# myPlant.net
KiCad netlist of a schematic drawn in EAGLE
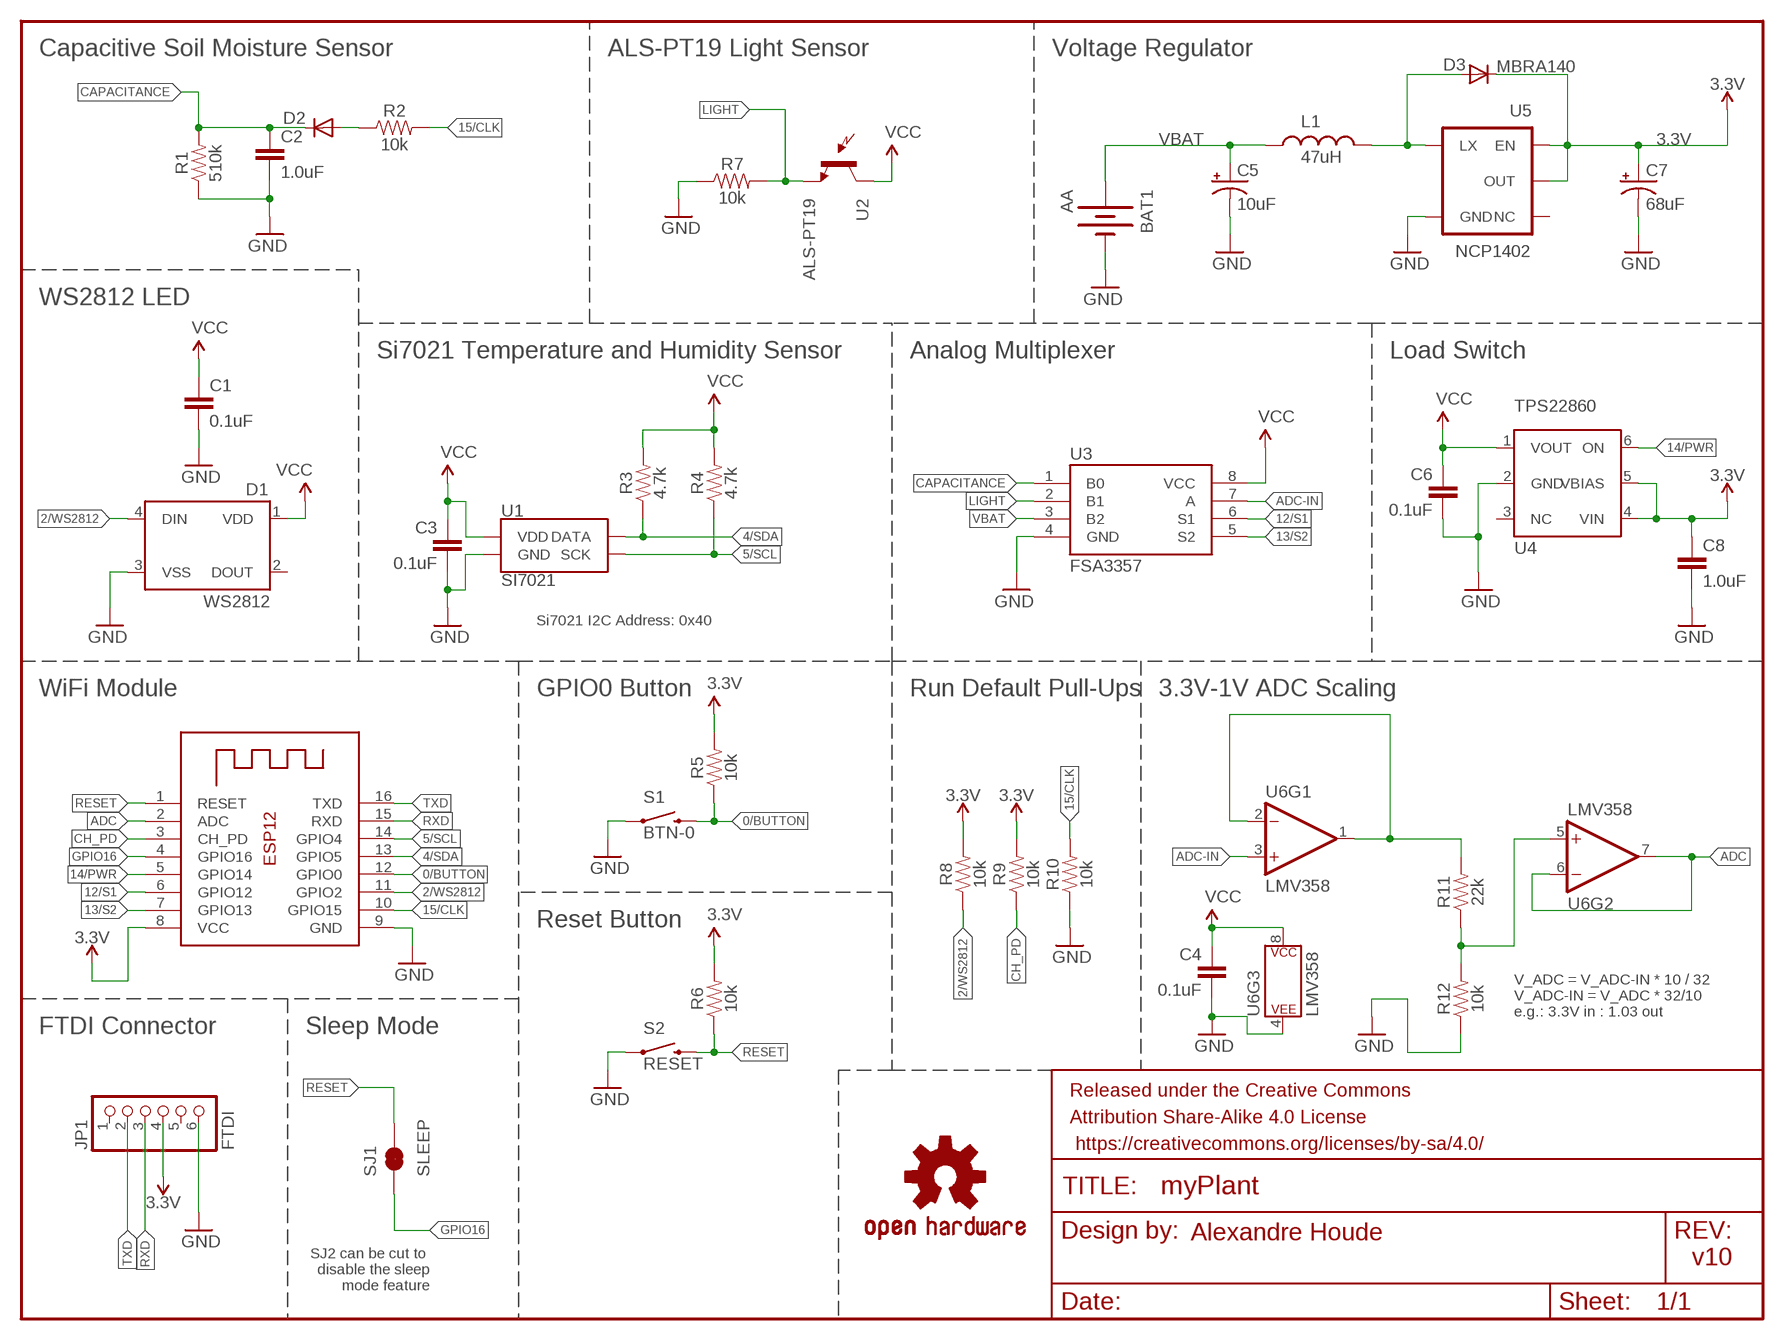
[diagram p0: schematic, sheet 1]

(export (version "E")
  (design (tool "Eeschema 10.0.6"))
  (components
    (comp (ref "BAT1")
      (value "AA")
      (footprint "eagle-import:BATTERY-AA-KIT")
      (libsource (lib "eagle-import") (part "BATTERYAA-KIT"))
    )
    (comp (ref "C1")
      (value "0.1uF")
      (footprint "eagle-import:0603")
      (libsource (lib "eagle-import") (part "0.1UF-0603-25V-(+80/-20%)"))
    )
    (comp (ref "C2")
      (value "1.0uF")
      (footprint "eagle-import:0603")
      (libsource (lib "eagle-import") (part "1.0UF-0603-16V-10%"))
    )
    (comp (ref "C3")
      (value "0.1uF")
      (footprint "eagle-import:0603")
      (libsource (lib "eagle-import") (part "0.1UF-0603-25V-(+80/-20%)"))
    )
    (comp (ref "C4")
      (value "0.1uF")
      (footprint "eagle-import:0603")
      (libsource (lib "eagle-import") (part "0.1UF-0603-25V-(+80/-20%)"))
    )
    (comp (ref "C5")
      (value "10uF")
      (footprint "eagle-import:EIA3216")
      (libsource (lib "eagle-import") (part "CAP_POL1206"))
    )
    (comp (ref "C6")
      (value "0.1uF")
      (footprint "eagle-import:0603")
      (libsource (lib "eagle-import") (part "0.1UF-0603-25V-(+80/-20%)"))
    )
    (comp (ref "C7")
      (value "68uF")
      (footprint "eagle-import:EIA3528")
      (libsource (lib "eagle-import") (part "CAP_POL3528"))
    )
    (comp (ref "C8")
      (value "1.0uF")
      (footprint "eagle-import:0603")
      (libsource (lib "eagle-import") (part "1.0UF-0603-16V-10%"))
    )
    (comp (ref "D1")
      (value "WS2812")
      (footprint "eagle-import:WS2812B")
      (libsource (lib "eagle-import") (part "WS2812B"))
    )
    (comp (ref "D2")
      (value "DIODE-SCHOTTKY_")
      (footprint "eagle-import:SOD-523")
      (libsource (lib "eagle-import") (part "DIODESOD-523"))
    )
    (comp (ref "D3")
      (value "MBRA140")
      (footprint "eagle-import:SMA-DIODE")
      (libsource (lib "eagle-import") (part "DIODESMA"))
    )
    (comp (ref "FRAME1")
      (value "FRAME-LETTER")
      (footprint "eagle-import:CREATIVE_COMMONS")
      (libsource (lib "eagle-import") (part "FRAME-LETTER"))
    )
    (comp (ref "JP1")
      (value "FTDI")
      (footprint "eagle-import:1X06_ROUND_70")
      (libsource (lib "eagle-import") (part "HEADER-1X670MIL"))
    )
    (comp (ref "L1")
      (value "47uH")
      (footprint "eagle-import:CR54")
      (libsource (lib "eagle-import") (part "INDUCTORCR54"))
    )
    (comp (ref "LOGO2")
      (value "OSHW-LOGOS")
      (footprint "eagle-import:OSHW-LOGO-S")
      (libsource (lib "eagle-import") (part "OSHW-LOGOS"))
    )
    (comp (ref "R1")
      (value "510k")
      (footprint "eagle-import:0603")
      (libsource (lib "eagle-import") (part "10KOHM-0603-1/10W-1%"))
    )
    (comp (ref "R2")
      (value "10k")
      (footprint "eagle-import:0603")
      (libsource (lib "eagle-import") (part "10KOHM-0603-1/10W-1%"))
    )
    (comp (ref "R3")
      (value "4.7k")
      (footprint "eagle-import:0603")
      (libsource (lib "eagle-import") (part "4.7KOHM-0603-1/10W-1%"))
    )
    (comp (ref "R4")
      (value "4.7k")
      (footprint "eagle-import:0603")
      (libsource (lib "eagle-import") (part "4.7KOHM-0603-1/10W-1%"))
    )
    (comp (ref "R5")
      (value "10k")
      (footprint "eagle-import:0603")
      (libsource (lib "eagle-import") (part "10KOHM-0603-1/10W-1%"))
    )
    (comp (ref "R6")
      (value "10k")
      (footprint "eagle-import:0603")
      (libsource (lib "eagle-import") (part "10KOHM-0603-1/10W-1%"))
    )
    (comp (ref "R7")
      (value "10k")
      (footprint "eagle-import:0603")
      (libsource (lib "eagle-import") (part "10KOHM-0603-1/10W-1%"))
    )
    (comp (ref "R8")
      (value "10k")
      (footprint "eagle-import:0603")
      (libsource (lib "eagle-import") (part "10KOHM-0603-1/10W-1%"))
    )
    (comp (ref "R9")
      (value "10k")
      (footprint "eagle-import:0603")
      (libsource (lib "eagle-import") (part "10KOHM-0603-1/10W-1%"))
    )
    (comp (ref "R10")
      (value "10k")
      (footprint "eagle-import:0603")
      (libsource (lib "eagle-import") (part "10KOHM-0603-1/10W-1%"))
    )
    (comp (ref "R11")
      (value "22k")
      (footprint "eagle-import:0603")
      (libsource (lib "eagle-import") (part "22KOHM-0603-1/10W-1%"))
    )
    (comp (ref "R12")
      (value "10k")
      (footprint "eagle-import:0603")
      (libsource (lib "eagle-import") (part "10KOHM-0603-1/10W-1%"))
    )
    (comp (ref "S1")
      (value "BTN-0")
      (footprint "eagle-import:TACTILE_SWITCH_SMD_4.6X2.8MM")
      (libsource (lib "eagle-import") (part "SWITCH-MOMENTARY-2SMD-4.6X2.8MM"))
    )
    (comp (ref "S2")
      (value "RESET")
      (footprint "eagle-import:TACTILE_SWITCH_SMD_4.6X2.8MM")
      (libsource (lib "eagle-import") (part "SWITCH-MOMENTARY-2SMD-4.6X2.8MM"))
    )
    (comp (ref "SJ1")
      (value "SLEEP")
      (footprint "eagle-import:PAD-JUMPER-2-NC_BY_TRACE_YES_SILK")
      (libsource (lib "eagle-import") (part "JUMPER-PAD-2-NC_BY_TRACE"))
    )
    (comp (ref "U1")
      (value "SI7021")
      (footprint "eagle-import:DFN-6-3X3-SI7021")
      (libsource (lib "eagle-import") (part "SI7021"))
    )
    (comp (ref "U2")
      (value "ALS-PT19")
      (footprint "eagle-import:ALS-PT19")
      (libsource (lib "eagle-import") (part "LIGHTSENSORALS"))
    )
    (comp (ref "U3")
      (value "FSA3357")
      (footprint "eagle-import:US8")
      (libsource (lib "eagle-import") (part "FSA3357"))
    )
    (comp (ref "U4")
      (value "TPS22860")
      (footprint "eagle-import:SOT23-6")
      (libsource (lib "eagle-import") (part "TPS22860"))
    )
    (comp (ref "U5")
      (value "NCP1402")
      (footprint "eagle-import:SOT23-5")
      (libsource (lib "eagle-import") (part "V_REG_NCP1400SOT23-5"))
    )
    (comp (ref "U6")
      (value "LMV358")
      (footprint "eagle-import:MSOP8")
      (libsource (lib "eagle-import") (part "LMV358"))
    )
    (comp (ref "X1")
      (value "ESP-12")
      (footprint "eagle-import:ESP-12")
      (libsource (lib "eagle-import") (part "ESP-12"))
    )
  )
  (nets
    (net (code "1") (name "0{slash}BUTTON") (class "Default")
      (node (ref "R5") (pin "1") (pinfunction "1_1") (pintype "passive"))
      (node (ref "S1") (pin "3") (pinfunction "2_3") (pintype "passive"))
      (node (ref "S1") (pin "4") (pinfunction "2_4") (pintype "passive"))
      (node (ref "X1") (pin "12") (pinfunction "GPIO0_12") (pintype "bidirectional"))
    )
    (net (code "2") (name "2{slash}WS2812") (class "Default")
      (node (ref "D1") (pin "4") (pinfunction "DIN_4") (pintype "input"))
      (node (ref "R8") (pin "1") (pinfunction "1_1") (pintype "passive"))
      (node (ref "X1") (pin "11") (pinfunction "GPIO2_11") (pintype "bidirectional"))
    )
    (net (code "3") (name "3.3V") (class "Default")
      (node (ref "C7") (pin "A") (pinfunction "+_A") (pintype "passive"))
      (node (ref "C8") (pin "1") (pinfunction "1_1") (pintype "passive"))
      (node (ref "D3") (pin "C") (pinfunction "C_C") (pintype "passive"))
      (node (ref "JP1") (pin "4") (pinfunction "4_4") (pintype "passive"))
      (node (ref "R5") (pin "2") (pinfunction "2_2") (pintype "passive"))
      (node (ref "R6") (pin "2") (pinfunction "2_2") (pintype "passive"))
      (node (ref "R8") (pin "2") (pinfunction "2_2") (pintype "passive"))
      (node (ref "R9") (pin "2") (pinfunction "2_2") (pintype "passive"))
      (node (ref "U4") (pin "4") (pinfunction "VIN_4") (pintype "bidirectional"))
      (node (ref "U4") (pin "5") (pinfunction "VBIAS_5") (pintype "bidirectional"))
      (node (ref "U5") (pin "1") (pinfunction "EN_1") (pintype "input"))
      (node (ref "U5") (pin "2") (pinfunction "OUT_2") (pintype "passive"))
      (node (ref "X1") (pin "8") (pinfunction "VCC_8") (pintype "power_in"))
    )
    (net (code "4") (name "4{slash}SDA") (class "Default")
      (node (ref "R3") (pin "1") (pinfunction "1_1") (pintype "passive"))
      (node (ref "U1") (pin "DATA") (pinfunction "DATA_DATA") (pintype "bidirectional"))
      (node (ref "X1") (pin "13") (pinfunction "GPIO5_13") (pintype "bidirectional"))
    )
    (net (code "5") (name "5{slash}SCL") (class "Default")
      (node (ref "R4") (pin "1") (pinfunction "1_1") (pintype "passive"))
      (node (ref "U1") (pin "SCK") (pinfunction "SCK_SCK") (pintype "input"))
      (node (ref "X1") (pin "14") (pinfunction "GPIO4_14") (pintype "bidirectional"))
    )
    (net (code "6") (name "12{slash}S1") (class "Default")
      (node (ref "U3") (pin "6") (pinfunction "S1_6") (pintype "bidirectional"))
      (node (ref "X1") (pin "6") (pinfunction "GPIO12_6") (pintype "bidirectional"))
    )
    (net (code "7") (name "13{slash}S2") (class "Default")
      (node (ref "U3") (pin "5") (pinfunction "S2_5") (pintype "bidirectional"))
      (node (ref "X1") (pin "7") (pinfunction "GPIO13_7") (pintype "bidirectional"))
    )
    (net (code "8") (name "14{slash}PWR") (class "Default")
      (node (ref "U4") (pin "6") (pinfunction "ON_6") (pintype "bidirectional"))
      (node (ref "X1") (pin "5") (pinfunction "GPIO14_5") (pintype "bidirectional"))
    )
    (net (code "9") (name "15{slash}CLK") (class "Default")
      (node (ref "R10") (pin "2") (pinfunction "2_2") (pintype "passive"))
      (node (ref "R2") (pin "2") (pinfunction "2_2") (pintype "passive"))
      (node (ref "X1") (pin "10") (pinfunction "GPIO15_10") (pintype "bidirectional"))
    )
    (net (code "10") (name "ADC") (class "Default")
      (node (ref "U6") (pin "6") (pinfunction "-IN_6") (pintype "input"))
      (node (ref "U6") (pin "7") (pinfunction "OUT_7") (pintype "output"))
      (node (ref "X1") (pin "2") (pinfunction "ADC_2") (pintype "passive"))
    )
    (net (code "11") (name "ADC-IN") (class "Default")
      (node (ref "U3") (pin "7") (pinfunction "A_7") (pintype "bidirectional"))
      (node (ref "U6") (pin "3") (pinfunction "+IN_3") (pintype "input"))
    )
    (net (code "12") (name "CAPACITANCE") (class "Default")
      (node (ref "C2") (pin "1") (pinfunction "1_1") (pintype "passive"))
      (node (ref "D2") (pin "K") (pinfunction "C_K") (pintype "passive"))
      (node (ref "R1") (pin "2") (pinfunction "2_2") (pintype "passive"))
      (node (ref "U3") (pin "1") (pinfunction "B0_1") (pintype "bidirectional"))
    )
    (net (code "13") (name "CH_PD") (class "Default")
      (node (ref "R9") (pin "1") (pinfunction "1_1") (pintype "passive"))
      (node (ref "X1") (pin "3") (pinfunction "CH_PD_3") (pintype "input"))
    )
    (net (code "14") (name "GND") (class "Default")
      (node (ref "BAT1") (pin "GND@1") (pinfunction "-_GND@1") (pintype "power_in"))
      (node (ref "C1") (pin "2") (pinfunction "2_2") (pintype "passive"))
      (node (ref "C2") (pin "2") (pinfunction "2_2") (pintype "passive"))
      (node (ref "C3") (pin "2") (pinfunction "2_2") (pintype "passive"))
      (node (ref "C4") (pin "2") (pinfunction "2_2") (pintype "passive"))
      (node (ref "C5") (pin "C") (pinfunction "-_C") (pintype "passive"))
      (node (ref "C6") (pin "2") (pinfunction "2_2") (pintype "passive"))
      (node (ref "C7") (pin "C") (pinfunction "-_C") (pintype "passive"))
      (node (ref "C8") (pin "2") (pinfunction "2_2") (pintype "passive"))
      (node (ref "D1") (pin "3") (pinfunction "VSS_3") (pintype "power_in"))
      (node (ref "JP1") (pin "6") (pinfunction "6_6") (pintype "passive"))
      (node (ref "R1") (pin "1") (pinfunction "1_1") (pintype "passive"))
      (node (ref "R10") (pin "1") (pinfunction "1_1") (pintype "passive"))
      (node (ref "R12") (pin "1") (pinfunction "1_1") (pintype "passive"))
      (node (ref "R7") (pin "1") (pinfunction "1_1") (pintype "passive"))
      (node (ref "S1") (pin "1") (pinfunction "1_1") (pintype "passive"))
      (node (ref "S1") (pin "2") (pinfunction "1_2") (pintype "passive"))
      (node (ref "S2") (pin "1") (pinfunction "1_1") (pintype "passive"))
      (node (ref "S2") (pin "2") (pinfunction "1_2") (pintype "passive"))
      (node (ref "U1") (pin "GND") (pinfunction "GND_GND") (pintype "power_in"))
      (node (ref "U3") (pin "4") (pinfunction "GND_4") (pintype "bidirectional"))
      (node (ref "U4") (pin "2") (pinfunction "GND_2") (pintype "bidirectional"))
      (node (ref "U5") (pin "4") (pinfunction "GND_4") (pintype "input"))
      (node (ref "U6") (pin "4") (pinfunction "P$V-_4") (pintype "bidirectional"))
      (node (ref "X1") (pin "9") (pinfunction "GND_9") (pintype "power_in"))
    )
    (net (code "15") (name "GPIO16") (class "Default")
      (node (ref "SJ1") (pin "1") (pinfunction "1_1") (pintype "passive"))
      (node (ref "X1") (pin "4") (pinfunction "GPIO16_4") (pintype "bidirectional"))
    )
    (net (code "16") (name "LIGHT") (class "Default")
      (node (ref "R7") (pin "2") (pinfunction "2_2") (pintype "passive"))
      (node (ref "U2") (pin "E") (pinfunction "E1_E") (pintype "passive"))
      (node (ref "U3") (pin "2") (pinfunction "B1_2") (pintype "bidirectional"))
    )
    (net (code "17") (name "Net-(D2-PadA)") (class "Default")
      (node (ref "D2") (pin "A") (pinfunction "A_A") (pintype "passive"))
      (node (ref "R2") (pin "1") (pinfunction "1_1") (pintype "passive"))
    )
    (net (code "18") (name "Net-(L1-2)") (class "Default")
      (node (ref "D3") (pin "A") (pinfunction "A_A") (pintype "passive"))
      (node (ref "L1") (pin "P$2") (pinfunction "2_P$2") (pintype "passive"))
      (node (ref "U5") (pin "5") (pinfunction "LX_5") (pintype "input"))
    )
    (net (code "19") (name "Net-(U6A--IN)") (class "Default")
      (node (ref "R11") (pin "2") (pinfunction "2_2") (pintype "passive"))
      (node (ref "U6") (pin "1") (pinfunction "OUT_1") (pintype "output"))
      (node (ref "U6") (pin "2") (pinfunction "-IN_2") (pintype "input"))
    )
    (net (code "20") (name "Net-(U6B-+IN)") (class "Default")
      (node (ref "R11") (pin "1") (pinfunction "1_1") (pintype "passive"))
      (node (ref "R12") (pin "2") (pinfunction "2_2") (pintype "passive"))
      (node (ref "U6") (pin "5") (pinfunction "+IN_5") (pintype "input"))
    )
    (net (code "21") (name "RESET") (class "Default")
      (node (ref "R6") (pin "1") (pinfunction "1_1") (pintype "passive"))
      (node (ref "S2") (pin "3") (pinfunction "2_3") (pintype "passive"))
      (node (ref "S2") (pin "4") (pinfunction "2_4") (pintype "passive"))
      (node (ref "SJ1") (pin "2") (pinfunction "2_2") (pintype "passive"))
      (node (ref "X1") (pin "1") (pinfunction "RESET_1") (pintype "input"))
    )
    (net (code "22") (name "RXD") (class "Default")
      (node (ref "JP1") (pin "3") (pinfunction "3_3") (pintype "passive"))
      (node (ref "X1") (pin "15") (pinfunction "RXD_15") (pintype "input"))
    )
    (net (code "23") (name "TXD") (class "Default")
      (node (ref "JP1") (pin "2") (pinfunction "2_2") (pintype "passive"))
      (node (ref "X1") (pin "16") (pinfunction "TXD_16") (pintype "output"))
    )
    (net (code "24") (name "VBAT") (class "Default")
      (node (ref "BAT1") (pin "PWR@1") (pinfunction "+_PWR@1") (pintype "power_in"))
      (node (ref "C5") (pin "A") (pinfunction "+_A") (pintype "passive"))
      (node (ref "L1") (pin "P$1") (pinfunction "1_P$1") (pintype "passive"))
      (node (ref "U3") (pin "3") (pinfunction "B2_3") (pintype "bidirectional"))
    )
    (net (code "25") (name "VCC") (class "Default")
      (node (ref "C1") (pin "1") (pinfunction "1_1") (pintype "passive"))
      (node (ref "C3") (pin "1") (pinfunction "1_1") (pintype "passive"))
      (node (ref "C4") (pin "1") (pinfunction "1_1") (pintype "passive"))
      (node (ref "C6") (pin "1") (pinfunction "1_1") (pintype "passive"))
      (node (ref "D1") (pin "1") (pinfunction "VDD_1") (pintype "power_in"))
      (node (ref "R3") (pin "2") (pinfunction "2_2") (pintype "passive"))
      (node (ref "R4") (pin "2") (pinfunction "2_2") (pintype "passive"))
      (node (ref "U1") (pin "VDD") (pinfunction "VDD_VDD") (pintype "power_in"))
      (node (ref "U2") (pin "C") (pinfunction "C1_C") (pintype "passive"))
      (node (ref "U3") (pin "8") (pinfunction "VCC_8") (pintype "bidirectional"))
      (node (ref "U4") (pin "1") (pinfunction "VOUT_1") (pintype "bidirectional"))
      (node (ref "U6") (pin "8") (pinfunction "P$V+_8") (pintype "bidirectional"))
    )
    (net (code "26") (name "unconnected-(D1-DOUT-Pad2)") (class "Default")
      (node (ref "D1") (pin "2") (pinfunction "DOUT_2") (pintype "output"))
    )
    (net (code "27") (name "unconnected-(JP1-Pad1)") (class "Default")
      (node (ref "JP1") (pin "1") (pinfunction "1_1") (pintype "passive"))
    )
    (net (code "28") (name "unconnected-(JP1-Pad5)") (class "Default")
      (node (ref "JP1") (pin "5") (pinfunction "5_5") (pintype "passive"))
    )
    (net (code "29") (name "unconnected-(U4-NC-Pad3)") (class "Default")
      (node (ref "U4") (pin "3") (pinfunction "NC_3") (pintype "bidirectional"))
    )
    (net (code "30") (name "unconnected-(U5-NC-Pad3)") (class "Default")
      (node (ref "U5") (pin "3") (pinfunction "NC_3") (pintype "input"))
    )
  )
)
